# atsha204-breakout.net
KiCad netlist of a schematic drawn in EAGLE
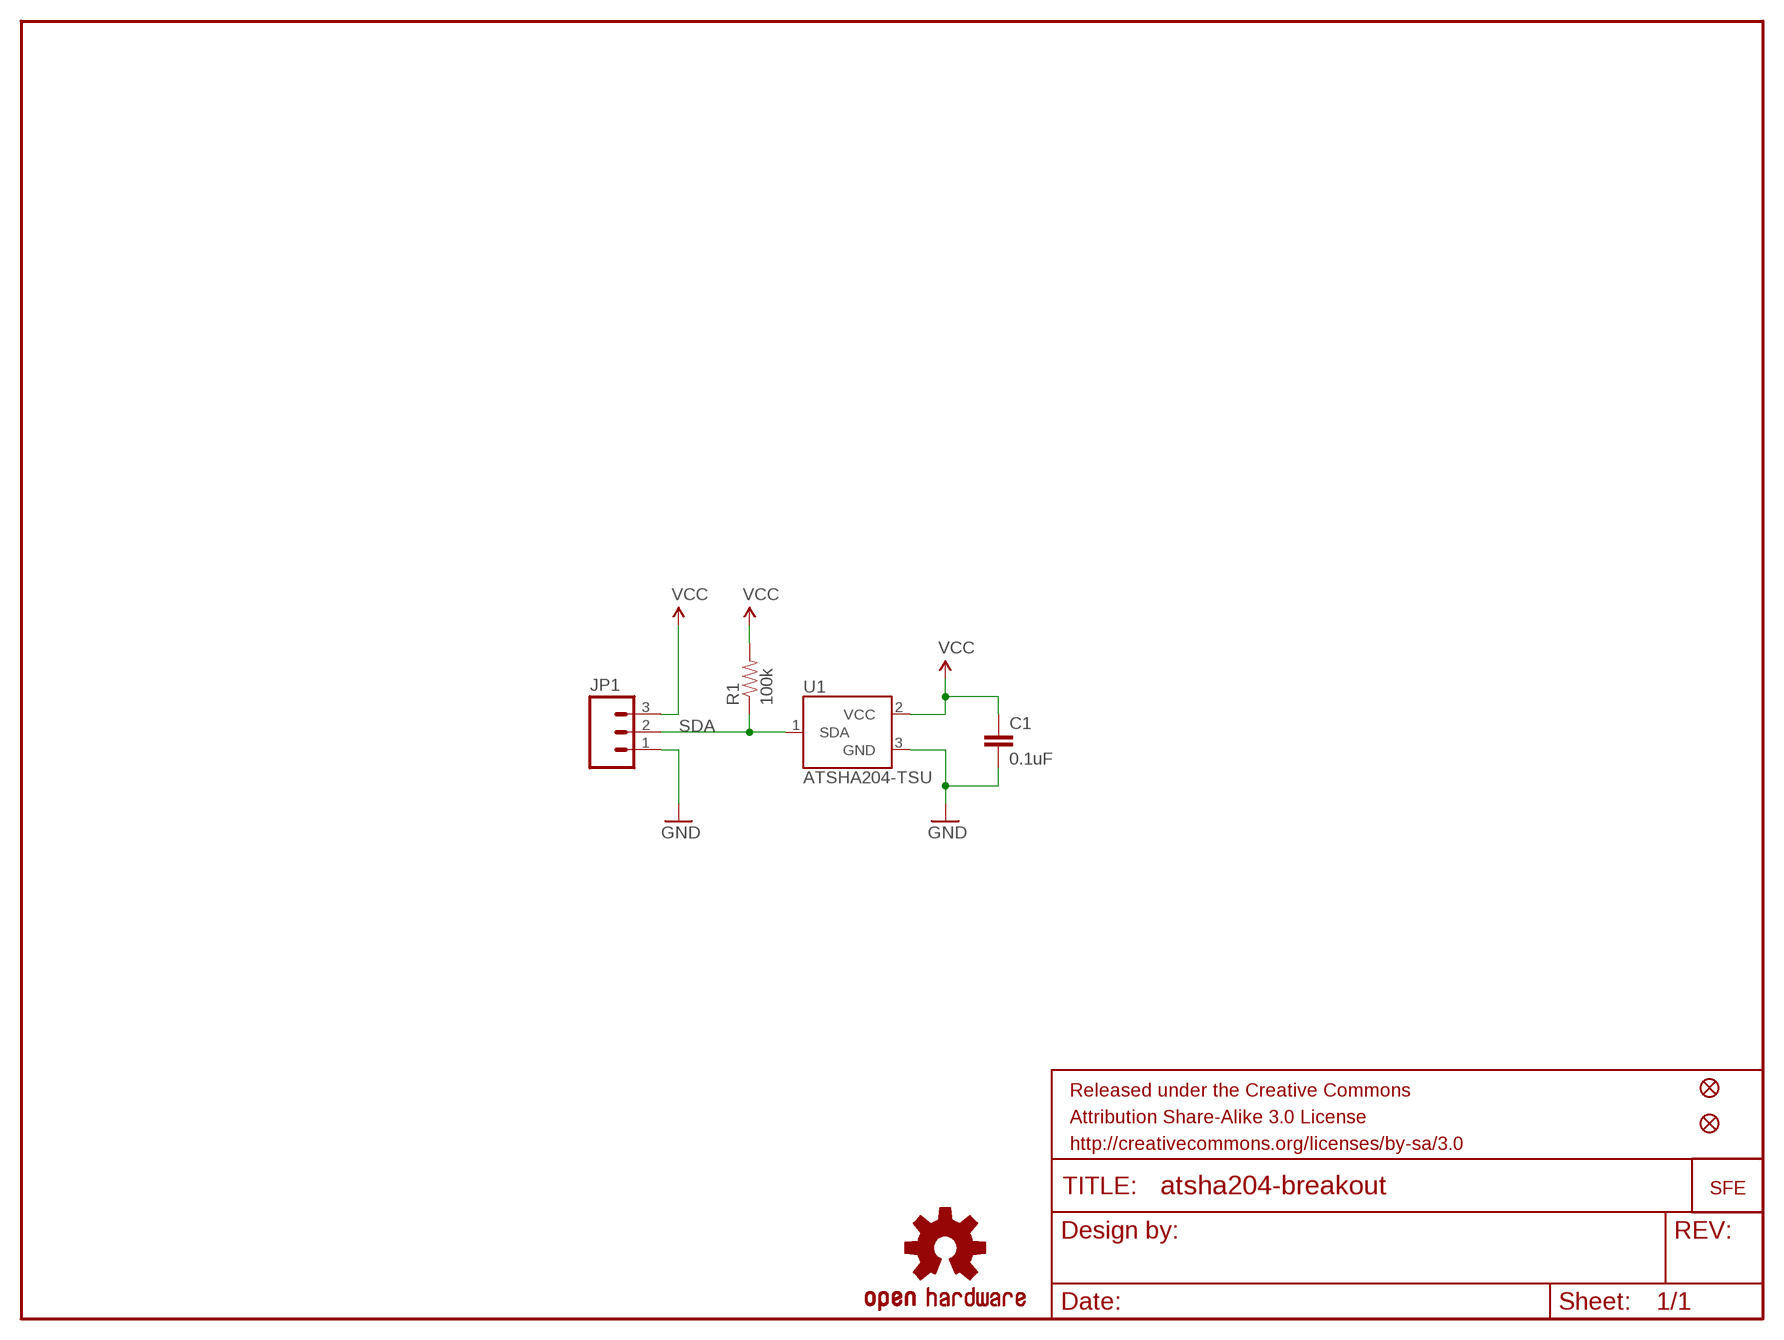
[diagram p0: schematic, sheet 1]

(export (version "E")
  (design (tool "Eeschema 10.0.6"))
  (components
    (comp (ref "C1")
      (value "0.1uF")
      (footprint "eagle-import:0402-CAP")
      (libsource (lib "eagle-import") (part "CAP0402-CAP"))
    )
    (comp (ref "JP1")
      (value "M031X03_NO_SILK")
      (footprint "eagle-import:1X03_NO_SILK")
      (libsource (lib "eagle-import") (part "M031X03_NO_SILK"))
    )
    (comp (ref "JP2")
      (value "LOGO-SFESK")
      (footprint "eagle-import:SFE-LOGO-FLAME")
      (libsource (lib "eagle-import") (part "LOGO-SFESK"))
    )
    (comp (ref "JP3")
      (value "FIDUCIALUFIDUCIAL")
      (footprint "eagle-import:MICRO-FIDUCIAL")
      (libsource (lib "eagle-import") (part "FIDUCIALUFIDUCIAL"))
    )
    (comp (ref "JP4")
      (value "FIDUCIALUFIDUCIAL")
      (footprint "eagle-import:MICRO-FIDUCIAL")
      (libsource (lib "eagle-import") (part "FIDUCIALUFIDUCIAL"))
    )
    (comp (ref "R1")
      (value "100k")
      (footprint "eagle-import:0402-RES")
      (libsource (lib "eagle-import") (part "RESISTOR0402-RES"))
    )
    (comp (ref "U$1")
      (value "OSHW-LOGOS")
      (footprint "eagle-import:OSHW-LOGO-S")
      (libsource (lib "eagle-import") (part "OSHW-LOGOS"))
    )
    (comp (ref "U1")
      (value "ATSHA204-TSU")
      (footprint "eagle-import:SOT23-3")
      (libsource (lib "eagle-import") (part "ATSHA204-TSU"))
    )
  )
  (nets
    (net (code "1") (name "/SDA") (class "Default")
      (node (ref "JP1") (pin "2") (pinfunction "2_2") (pintype "passive"))
      (node (ref "R1") (pin "1") (pinfunction "1_1") (pintype "passive"))
      (node (ref "U1") (pin "1") (pinfunction "SDA_1") (pintype "bidirectional"))
    )
    (net (code "2") (name "GND") (class "Default")
      (node (ref "C1") (pin "2") (pinfunction "2_2") (pintype "passive"))
      (node (ref "JP1") (pin "1") (pinfunction "1_1") (pintype "passive"))
      (node (ref "U1") (pin "3") (pinfunction "GND_3") (pintype "bidirectional"))
    )
    (net (code "3") (name "VCC") (class "Default")
      (node (ref "C1") (pin "1") (pinfunction "1_1") (pintype "passive"))
      (node (ref "JP1") (pin "3") (pinfunction "3_3") (pintype "passive"))
      (node (ref "R1") (pin "2") (pinfunction "2_2") (pintype "passive"))
      (node (ref "U1") (pin "2") (pinfunction "VCC_2") (pintype "bidirectional"))
    )
  )
)
